# RP2040_Minimal.net
KiCad netlist of a schematic drawn in EAGLE
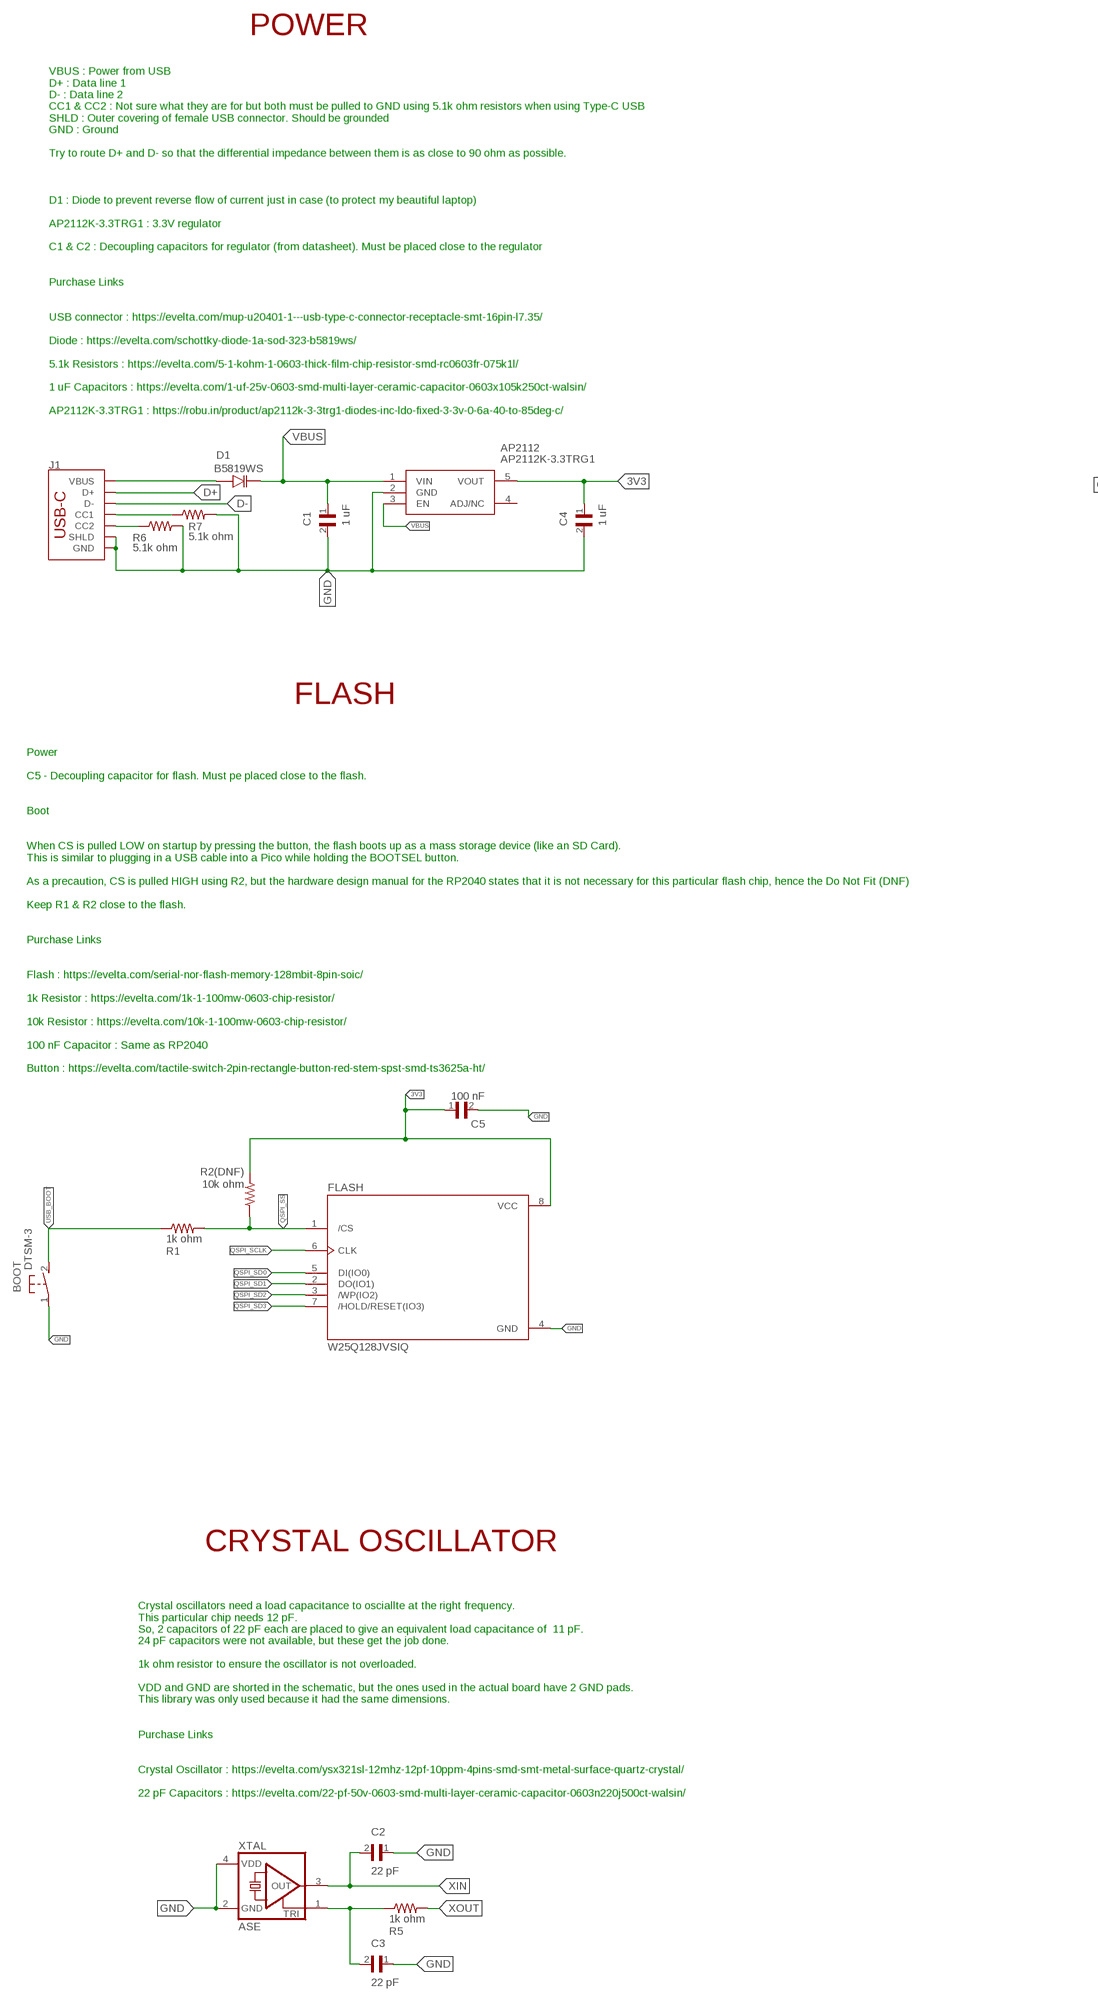
[diagram p0: schematic, sheet 1, part 1 of 2]
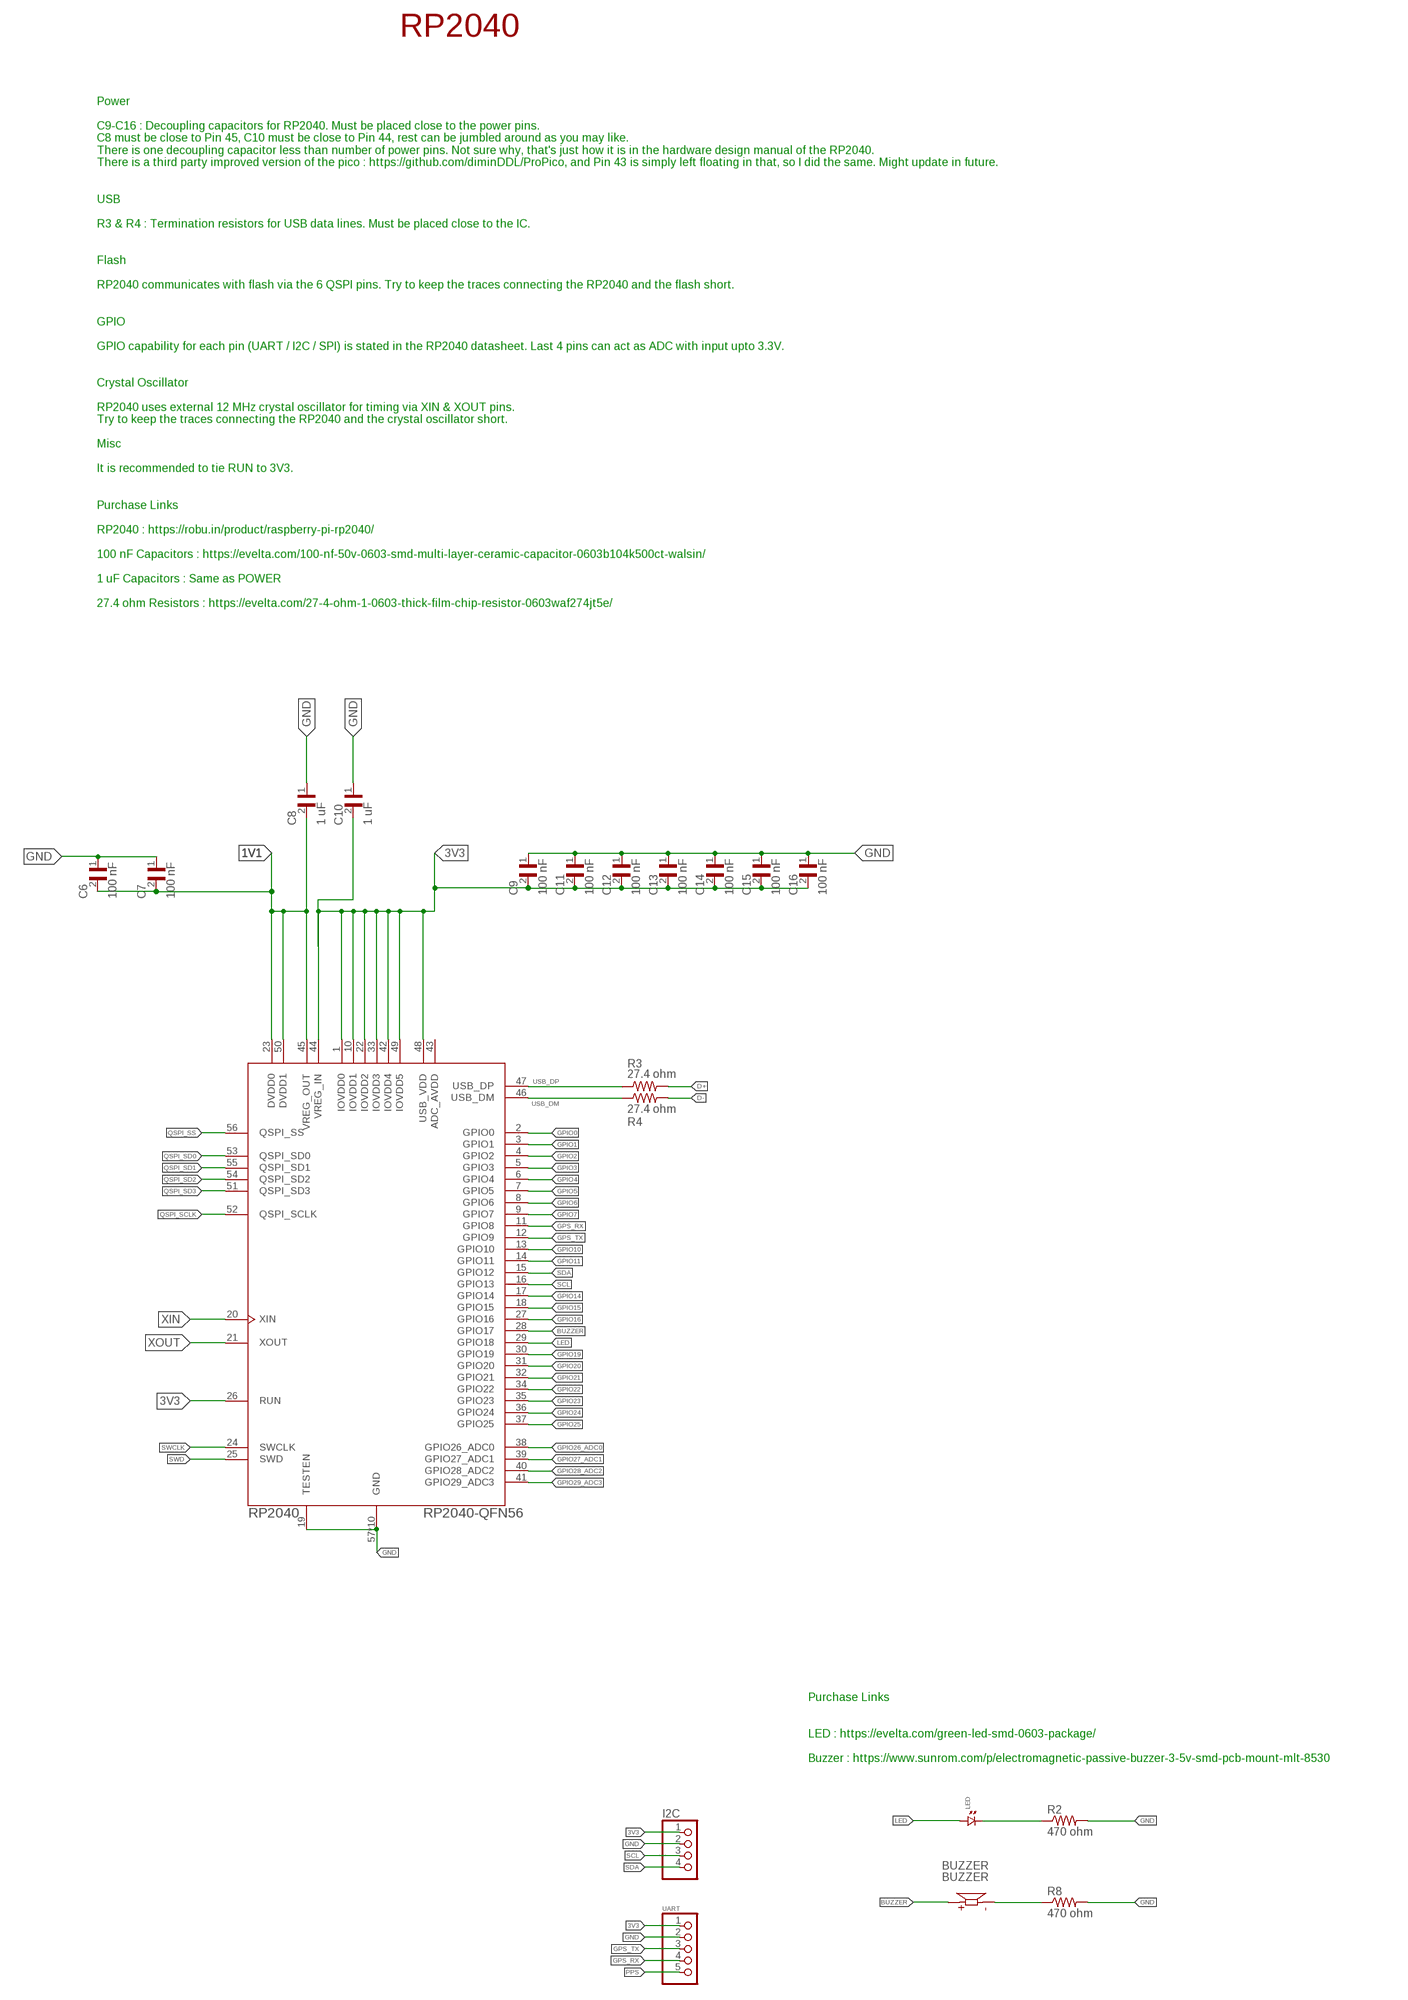
[diagram p1: schematic, sheet 1, part 2 of 2]

(export (version "E")
  (design (tool "Eeschema 10.0.6"))
  (components
    (comp (ref "AP2112")
      (value "AP2112K-3.3TRG1")
      (footprint "eagle-import:SOT95P282X130-5N")
      (fields (field (name "MOUSER_PART_NUMBER") "621-AP2112K-3.3TRG1"))
      (libsource (lib "eagle-import") (part "AP2112K-3.3TRG1"))
    )
    (comp (ref "BOOT")
      (value "DTSM-3")
      (footprint "eagle-import:DTSM-3")
      (libsource (lib "eagle-import") (part "DTSM-3"))
    )
    (comp (ref "BUZZER")
      (value "BUZZER")
      (footprint "eagle-import:CUI_CMT-8530S-SMT")
      (fields (field (name "MF") "CUI Devices") (field (name "MP") "CMT-8530S-SMT-TR"))
      (libsource (lib "eagle-import") (part "CMT-8530S-SMT"))
    )
    (comp (ref "C1")
      (value "1 uF")
      (footprint "eagle-import:CAPC1608X90")
      (fields (field (name "MF") "Yageo") (field (name "MP") "CC0603KRX7R9BB104"))
      (libsource (lib "eagle-import") (part "CC0603KRX7R9BB104"))
    )
    (comp (ref "C2")
      (value "22 pF")
      (footprint "eagle-import:CAPC1608X90")
      (fields (field (name "MF") "Yageo") (field (name "MP") "CC0603KRX7R9BB104"))
      (libsource (lib "eagle-import") (part "CC0603KRX7R9BB104"))
    )
    (comp (ref "C3")
      (value "22 pF")
      (footprint "eagle-import:CAPC1608X90")
      (fields (field (name "MF") "Yageo") (field (name "MP") "CC0603KRX7R9BB104"))
      (libsource (lib "eagle-import") (part "CC0603KRX7R9BB104"))
    )
    (comp (ref "C4")
      (value "1 uF")
      (footprint "eagle-import:CAPC1608X90")
      (fields (field (name "MF") "Yageo") (field (name "MP") "CC0603KRX7R9BB104"))
      (libsource (lib "eagle-import") (part "CC0603KRX7R9BB104"))
    )
    (comp (ref "C5")
      (value "100 nF")
      (footprint "eagle-import:CAPC1608X90")
      (fields (field (name "MF") "Yageo") (field (name "MP") "CC0603KRX7R9BB104"))
      (libsource (lib "eagle-import") (part "CC0603KRX7R9BB104"))
    )
    (comp (ref "C6")
      (value "100 nF")
      (footprint "eagle-import:CAPC1608X90")
      (fields (field (name "MF") "Yageo") (field (name "MP") "CC0603KRX7R9BB104"))
      (libsource (lib "eagle-import") (part "CC0603KRX7R9BB104"))
    )
    (comp (ref "C7")
      (value "100 nF")
      (footprint "eagle-import:CAPC1608X90")
      (fields (field (name "MF") "Yageo") (field (name "MP") "CC0603KRX7R9BB104"))
      (libsource (lib "eagle-import") (part "CC0603KRX7R9BB104"))
    )
    (comp (ref "C8")
      (value "1 uF")
      (footprint "eagle-import:CAPC1608X90")
      (fields (field (name "MF") "Yageo") (field (name "MP") "CC0603KRX7R9BB104"))
      (libsource (lib "eagle-import") (part "CC0603KRX7R9BB104"))
    )
    (comp (ref "C9")
      (value "100 nF")
      (footprint "eagle-import:CAPC1608X90")
      (fields (field (name "MF") "Yageo") (field (name "MP") "CC0603KRX7R9BB104"))
      (libsource (lib "eagle-import") (part "CC0603KRX7R9BB104"))
    )
    (comp (ref "C10")
      (value "1 uF")
      (footprint "eagle-import:CAPC1608X90")
      (fields (field (name "MF") "Yageo") (field (name "MP") "CC0603KRX7R9BB104"))
      (libsource (lib "eagle-import") (part "CC0603KRX7R9BB104"))
    )
    (comp (ref "C11")
      (value "100 nF")
      (footprint "eagle-import:CAPC1608X90")
      (fields (field (name "MF") "Yageo") (field (name "MP") "CC0603KRX7R9BB104"))
      (libsource (lib "eagle-import") (part "CC0603KRX7R9BB104"))
    )
    (comp (ref "C12")
      (value "100 nF")
      (footprint "eagle-import:CAPC1608X90")
      (fields (field (name "MF") "Yageo") (field (name "MP") "CC0603KRX7R9BB104"))
      (libsource (lib "eagle-import") (part "CC0603KRX7R9BB104"))
    )
    (comp (ref "C13")
      (value "100 nF")
      (footprint "eagle-import:CAPC1608X90")
      (fields (field (name "MF") "Yageo") (field (name "MP") "CC0603KRX7R9BB104"))
      (libsource (lib "eagle-import") (part "CC0603KRX7R9BB104"))
    )
    (comp (ref "C14")
      (value "100 nF")
      (footprint "eagle-import:CAPC1608X90")
      (fields (field (name "MF") "Yageo") (field (name "MP") "CC0603KRX7R9BB104"))
      (libsource (lib "eagle-import") (part "CC0603KRX7R9BB104"))
    )
    (comp (ref "C15")
      (value "100 nF")
      (footprint "eagle-import:CAPC1608X90")
      (fields (field (name "MF") "Yageo") (field (name "MP") "CC0603KRX7R9BB104"))
      (libsource (lib "eagle-import") (part "CC0603KRX7R9BB104"))
    )
    (comp (ref "C16")
      (value "100 nF")
      (footprint "eagle-import:CAPC1608X90")
      (fields (field (name "MF") "Yageo") (field (name "MP") "CC0603KRX7R9BB104"))
      (libsource (lib "eagle-import") (part "CC0603KRX7R9BB104"))
    )
    (comp (ref "D1")
      (value "B5819WS")
      (footprint "eagle-import:SOD2512X116N")
      (fields (field (name "MF") "Diodes Inc.") (field (name "MP") "ZMV829BTA"))
      (libsource (lib "eagle-import") (part "ZMV829BTA"))
    )
    (comp (ref "FLASH")
      (value "W25Q128JVSIQ")
      (footprint "eagle-import:SOIC127P790X216-8N")
      (fields (field (name "MF") "Winbond Electronics"))
      (libsource (lib "eagle-import") (part "W25Q128JVSIQ"))
    )
    (comp (ref "I2C")
      (value "PINHD-1X4")
      (footprint "eagle-import:1X04")
      (libsource (lib "eagle-import") (part "PINHD-1X4"))
    )
    (comp (ref "J1")
      (value "USB_C_2-LAYER_PADS")
      (footprint "eagle-import:USB-C-16P-2LAYER-PADS")
      (libsource (lib "eagle-import") (part "USB_C_2-LAYER_PADS"))
    )
    (comp (ref "LED")
      (value "LED.0603")
      (footprint "eagle-import:0603.LED")
      (libsource (lib "eagle-import") (part "LED.0603"))
    )
    (comp (ref "R1")
      (value "1k ohm")
      (footprint "eagle-import:RESC1608X50N")
      (fields
        (field (name "COMMENT") "2-1879338-7")
        (field (name "MF") "TE Connectivity")
        (field (name "MP") "CPF0603F49K9C1")
      )
      (libsource (lib "eagle-import") (part "CPF0603F49K9C1"))
    )
    (comp (ref "R2")
      (value "470 ohm")
      (footprint "eagle-import:RESC1608X50N")
      (fields
        (field (name "COMMENT") "2-1879338-7")
        (field (name "MF") "TE Connectivity")
        (field (name "MP") "CPF0603F49K9C1")
      )
      (libsource (lib "eagle-import") (part "CPF0603F49K9C1"))
    )
    (comp (ref "R2(DNF)")
      (value "10k ohm")
      (footprint "eagle-import:RESC1608X50N")
      (fields
        (field (name "COMMENT") "2-1879338-7")
        (field (name "MF") "TE Connectivity")
        (field (name "MP") "CPF0603F49K9C1")
      )
      (libsource (lib "eagle-import") (part "CPF0603F49K9C1"))
    )
    (comp (ref "R3")
      (value "27.4 ohm")
      (footprint "eagle-import:RESC1608X50N")
      (fields
        (field (name "COMMENT") "2-1879338-7")
        (field (name "MF") "TE Connectivity")
        (field (name "MP") "CPF0603F49K9C1")
      )
      (libsource (lib "eagle-import") (part "CPF0603F49K9C1"))
    )
    (comp (ref "R4")
      (value "27.4 ohm")
      (footprint "eagle-import:RESC1608X50N")
      (fields
        (field (name "COMMENT") "2-1879338-7")
        (field (name "MF") "TE Connectivity")
        (field (name "MP") "CPF0603F49K9C1")
      )
      (libsource (lib "eagle-import") (part "CPF0603F49K9C1"))
    )
    (comp (ref "R5")
      (value "1k ohm")
      (footprint "eagle-import:RESC1608X50N")
      (fields
        (field (name "COMMENT") "2-1879338-7")
        (field (name "MF") "TE Connectivity")
        (field (name "MP") "CPF0603F49K9C1")
      )
      (libsource (lib "eagle-import") (part "CPF0603F49K9C1"))
    )
    (comp (ref "R6")
      (value "5.1k ohm")
      (footprint "eagle-import:RESC1608X50N")
      (fields
        (field (name "COMMENT") "2-1879338-7")
        (field (name "MF") "TE Connectivity")
        (field (name "MP") "CPF0603F49K9C1")
      )
      (libsource (lib "eagle-import") (part "CPF0603F49K9C1"))
    )
    (comp (ref "R7")
      (value "5.1k ohm")
      (footprint "eagle-import:RESC1608X50N")
      (fields
        (field (name "COMMENT") "2-1879338-7")
        (field (name "MF") "TE Connectivity")
        (field (name "MP") "CPF0603F49K9C1")
      )
      (libsource (lib "eagle-import") (part "CPF0603F49K9C1"))
    )
    (comp (ref "R8")
      (value "470 ohm")
      (footprint "eagle-import:RESC1608X50N")
      (fields
        (field (name "COMMENT") "2-1879338-7")
        (field (name "MF") "TE Connectivity")
        (field (name "MP") "CPF0603F49K9C1")
      )
      (libsource (lib "eagle-import") (part "CPF0603F49K9C1"))
    )
    (comp (ref "RP2040")
      (value "RP2040-QFN56")
      (footprint "eagle-import:RP2040-QFN-56")
      (libsource (lib "eagle-import") (part "RP2040-QFN56"))
    )
    (comp (ref "UART")
      (value "PINHD-1X5")
      (footprint "eagle-import:1X05")
      (libsource (lib "eagle-import") (part "PINHD-1X5"))
    )
    (comp (ref "XTAL")
      (value "ASE")
      (footprint "eagle-import:ASE")
      (libsource (lib "eagle-import") (part "ASE"))
    )
  )
  (nets
    (net (code "1") (name "/ADC_AVDD") (class "Default")
      (node (ref "RP2040") (pin "43") (pinfunction "ADC_AVDD_43") (pintype "power_in"))
    )
    (net (code "2") (name "/USB_DM") (class "Default")
      (node (ref "R4") (pin "1") (pinfunction "1_1") (pintype "passive"))
      (node (ref "RP2040") (pin "46") (pinfunction "USB_DM_46") (pintype "bidirectional"))
    )
    (net (code "3") (name "/USB_DP") (class "Default")
      (node (ref "R3") (pin "1") (pinfunction "1_1") (pintype "passive"))
      (node (ref "RP2040") (pin "47") (pinfunction "USB_DP_47") (pintype "bidirectional"))
    )
    (net (code "4") (name "1V1") (class "Default")
      (node (ref "C6") (pin "2") (pinfunction "2_2") (pintype "passive"))
      (node (ref "C7") (pin "2") (pinfunction "2_2") (pintype "passive"))
      (node (ref "C8") (pin "2") (pinfunction "2_2") (pintype "passive"))
      (node (ref "RP2040") (pin "23") (pinfunction "DVDD0_23") (pintype "power_in"))
      (node (ref "RP2040") (pin "45") (pinfunction "VREG_OUT_45") (pintype "power_in"))
      (node (ref "RP2040") (pin "50") (pinfunction "DVDD1_50") (pintype "power_in"))
    )
    (net (code "5") (name "3V3") (class "Default")
      (node (ref "AP2112") (pin "5") (pinfunction "VOUT_5") (pintype "bidirectional"))
      (node (ref "C10") (pin "2") (pinfunction "2_2") (pintype "passive"))
      (node (ref "C11") (pin "2") (pinfunction "2_2") (pintype "passive"))
      (node (ref "C12") (pin "2") (pinfunction "2_2") (pintype "passive"))
      (node (ref "C13") (pin "2") (pinfunction "2_2") (pintype "passive"))
      (node (ref "C14") (pin "2") (pinfunction "2_2") (pintype "passive"))
      (node (ref "C15") (pin "2") (pinfunction "2_2") (pintype "passive"))
      (node (ref "C16") (pin "2") (pinfunction "2_2") (pintype "passive"))
      (node (ref "C4") (pin "1") (pinfunction "1_1") (pintype "passive"))
      (node (ref "C5") (pin "1") (pinfunction "1_1") (pintype "passive"))
      (node (ref "C9") (pin "2") (pinfunction "2_2") (pintype "passive"))
      (node (ref "FLASH") (pin "8") (pinfunction "VCC_8") (pintype "power_in"))
      (node (ref "I2C") (pin "1") (pinfunction "1_1") (pintype "passive"))
      (node (ref "R2(DNF)") (pin "2") (pinfunction "2_2") (pintype "passive"))
      (node (ref "RP2040") (pin "1") (pinfunction "IOVDD0_1") (pintype "power_in"))
      (node (ref "RP2040") (pin "10") (pinfunction "IOVDD1_10") (pintype "power_in"))
      (node (ref "RP2040") (pin "22") (pinfunction "IOVDD2_22") (pintype "power_in"))
      (node (ref "RP2040") (pin "26") (pinfunction "RUN_26") (pintype "input"))
      (node (ref "RP2040") (pin "33") (pinfunction "IOVDD3_33") (pintype "power_in"))
      (node (ref "RP2040") (pin "42") (pinfunction "IOVDD4_42") (pintype "power_in"))
      (node (ref "RP2040") (pin "44") (pinfunction "VREG_IN_44") (pintype "power_in"))
      (node (ref "RP2040") (pin "48") (pinfunction "USB_VDD_48") (pintype "power_in"))
      (node (ref "RP2040") (pin "49") (pinfunction "IOVDD5_49") (pintype "power_in"))
      (node (ref "UART") (pin "1") (pinfunction "1_1") (pintype "passive"))
    )
    (net (code "6") (name "BUZZER") (class "Default")
      (node (ref "BUZZER") (pin "P") (pinfunction "P_P") (pintype "passive"))
      (node (ref "RP2040") (pin "28") (pinfunction "GPIO17_28") (pintype "bidirectional"))
    )
    (net (code "7") (name "D+") (class "Default")
      (node (ref "J1") (pin "A6") (pinfunction "D+_A6") (pintype "bidirectional"))
      (node (ref "J1") (pin "B6") (pinfunction "D+_B6") (pintype "bidirectional"))
      (node (ref "R3") (pin "2") (pinfunction "2_2") (pintype "passive"))
    )
    (net (code "8") (name "D-") (class "Default")
      (node (ref "J1") (pin "A7") (pinfunction "D-_A7") (pintype "bidirectional"))
      (node (ref "J1") (pin "B7") (pinfunction "D-_B7") (pintype "bidirectional"))
      (node (ref "R4") (pin "2") (pinfunction "2_2") (pintype "passive"))
    )
    (net (code "9") (name "GND") (class "Default")
      (node (ref "AP2112") (pin "2") (pinfunction "GND_2") (pintype "bidirectional"))
      (node (ref "BOOT") (pin "1") (pinfunction "1_1") (pintype "passive"))
      (node (ref "C1") (pin "2") (pinfunction "2_2") (pintype "passive"))
      (node (ref "C10") (pin "1") (pinfunction "1_1") (pintype "passive"))
      (node (ref "C11") (pin "1") (pinfunction "1_1") (pintype "passive"))
      (node (ref "C12") (pin "1") (pinfunction "1_1") (pintype "passive"))
      (node (ref "C13") (pin "1") (pinfunction "1_1") (pintype "passive"))
      (node (ref "C14") (pin "1") (pinfunction "1_1") (pintype "passive"))
      (node (ref "C15") (pin "1") (pinfunction "1_1") (pintype "passive"))
      (node (ref "C16") (pin "1") (pinfunction "1_1") (pintype "passive"))
      (node (ref "C2") (pin "1") (pinfunction "1_1") (pintype "passive"))
      (node (ref "C3") (pin "1") (pinfunction "1_1") (pintype "passive"))
      (node (ref "C4") (pin "2") (pinfunction "2_2") (pintype "passive"))
      (node (ref "C5") (pin "2") (pinfunction "2_2") (pintype "passive"))
      (node (ref "C6") (pin "1") (pinfunction "1_1") (pintype "passive"))
      (node (ref "C7") (pin "1") (pinfunction "1_1") (pintype "passive"))
      (node (ref "C8") (pin "1") (pinfunction "1_1") (pintype "passive"))
      (node (ref "C9") (pin "1") (pinfunction "1_1") (pintype "passive"))
      (node (ref "FLASH") (pin "4") (pinfunction "GND_4") (pintype "power_in"))
      (node (ref "I2C") (pin "2") (pinfunction "2_2") (pintype "passive"))
      (node (ref "J1") (pin "GND") (pinfunction "GND_GND") (pintype "bidirectional"))
      (node (ref "J1") (pin "GND2") (pinfunction "GND_GND2") (pintype "bidirectional"))
      (node (ref "J1") (pin "SHLD1") (pinfunction "SHLD_SHLD1") (pintype "bidirectional"))
      (node (ref "J1") (pin "SHLD2") (pinfunction "SHLD_SHLD2") (pintype "bidirectional"))
      (node (ref "J1") (pin "SHLD3") (pinfunction "SHLD_SHLD3") (pintype "bidirectional"))
      (node (ref "J1") (pin "SHLD4") (pinfunction "SHLD_SHLD4") (pintype "bidirectional"))
      (node (ref "R2") (pin "2") (pinfunction "2_2") (pintype "passive"))
      (node (ref "R6") (pin "2") (pinfunction "2_2") (pintype "passive"))
      (node (ref "R7") (pin "2") (pinfunction "2_2") (pintype "passive"))
      (node (ref "R8") (pin "2") (pinfunction "2_2") (pintype "passive"))
      (node (ref "RP2040") (pin "19") (pinfunction "TESTEN_19") (pintype "passive"))
      (node (ref "RP2040") (pin "57") (pinfunction "GND_57") (pintype "power_in"))
      (node (ref "RP2040") (pin "58") (pinfunction "GND_58") (pintype "power_in"))
      (node (ref "RP2040") (pin "59") (pinfunction "GND_59") (pintype "power_in"))
      (node (ref "RP2040") (pin "60") (pinfunction "GND_60") (pintype "power_in"))
      (node (ref "RP2040") (pin "61") (pinfunction "GND_61") (pintype "power_in"))
      (node (ref "RP2040") (pin "62") (pinfunction "GND_62") (pintype "power_in"))
      (node (ref "RP2040") (pin "63") (pinfunction "GND_63") (pintype "power_in"))
      (node (ref "RP2040") (pin "64") (pinfunction "GND_64") (pintype "power_in"))
      (node (ref "RP2040") (pin "65") (pinfunction "GND_65") (pintype "power_in"))
      (node (ref "RP2040") (pin "66") (pinfunction "GND_66") (pintype "power_in"))
      (node (ref "UART") (pin "2") (pinfunction "2_2") (pintype "passive"))
      (node (ref "XTAL") (pin "2") (pinfunction "GND_2") (pintype "power_in"))
      (node (ref "XTAL") (pin "4") (pinfunction "VDD_4") (pintype "power_in"))
    )
    (net (code "10") (name "GPIO0") (class "Default")
      (node (ref "RP2040") (pin "2") (pinfunction "GPIO0_2") (pintype "bidirectional"))
    )
    (net (code "11") (name "GPIO1") (class "Default")
      (node (ref "RP2040") (pin "3") (pinfunction "GPIO1_3") (pintype "bidirectional"))
    )
    (net (code "12") (name "GPIO2") (class "Default")
      (node (ref "RP2040") (pin "4") (pinfunction "GPIO2_4") (pintype "bidirectional"))
    )
    (net (code "13") (name "GPIO3") (class "Default")
      (node (ref "RP2040") (pin "5") (pinfunction "GPIO3_5") (pintype "bidirectional"))
    )
    (net (code "14") (name "GPIO4") (class "Default")
      (node (ref "RP2040") (pin "6") (pinfunction "GPIO4_6") (pintype "bidirectional"))
    )
    (net (code "15") (name "GPIO5") (class "Default")
      (node (ref "RP2040") (pin "7") (pinfunction "GPIO5_7") (pintype "bidirectional"))
    )
    (net (code "16") (name "GPIO6") (class "Default")
      (node (ref "RP2040") (pin "8") (pinfunction "GPIO6_8") (pintype "bidirectional"))
    )
    (net (code "17") (name "GPIO7") (class "Default")
      (node (ref "RP2040") (pin "9") (pinfunction "GPIO7_9") (pintype "bidirectional"))
    )
    (net (code "18") (name "GPIO10") (class "Default")
      (node (ref "RP2040") (pin "13") (pinfunction "GPIO10_13") (pintype "bidirectional"))
    )
    (net (code "19") (name "GPIO11") (class "Default")
      (node (ref "RP2040") (pin "14") (pinfunction "GPIO11_14") (pintype "bidirectional"))
    )
    (net (code "20") (name "GPIO14") (class "Default")
      (node (ref "RP2040") (pin "17") (pinfunction "GPIO14_17") (pintype "bidirectional"))
    )
    (net (code "21") (name "GPIO15") (class "Default")
      (node (ref "RP2040") (pin "18") (pinfunction "GPIO15_18") (pintype "bidirectional"))
    )
    (net (code "22") (name "GPIO16") (class "Default")
      (node (ref "RP2040") (pin "27") (pinfunction "GPIO16_27") (pintype "bidirectional"))
    )
    (net (code "23") (name "GPIO19") (class "Default")
      (node (ref "RP2040") (pin "30") (pinfunction "GPIO19_30") (pintype "bidirectional"))
    )
    (net (code "24") (name "GPIO20") (class "Default")
      (node (ref "RP2040") (pin "31") (pinfunction "GPIO20_31") (pintype "bidirectional"))
    )
    (net (code "25") (name "GPIO21") (class "Default")
      (node (ref "RP2040") (pin "32") (pinfunction "GPIO21_32") (pintype "bidirectional"))
    )
    (net (code "26") (name "GPIO22") (class "Default")
      (node (ref "RP2040") (pin "34") (pinfunction "GPIO22_34") (pintype "bidirectional"))
    )
    (net (code "27") (name "GPIO23") (class "Default")
      (node (ref "RP2040") (pin "35") (pinfunction "GPIO23_35") (pintype "bidirectional"))
    )
    (net (code "28") (name "GPIO24") (class "Default")
      (node (ref "RP2040") (pin "36") (pinfunction "GPIO24_36") (pintype "bidirectional"))
    )
    (net (code "29") (name "GPIO25") (class "Default")
      (node (ref "RP2040") (pin "37") (pinfunction "GPIO25_37") (pintype "bidirectional"))
    )
    (net (code "30") (name "GPIO26_ADC0") (class "Default")
      (node (ref "RP2040") (pin "38") (pinfunction "GPIO26_ADC0_38") (pintype "bidirectional"))
    )
    (net (code "31") (name "GPIO27_ADC1") (class "Default")
      (node (ref "RP2040") (pin "39") (pinfunction "GPIO27_ADC1_39") (pintype "bidirectional"))
    )
    (net (code "32") (name "GPIO28_ADC2") (class "Default")
      (node (ref "RP2040") (pin "40") (pinfunction "GPIO28_ADC2_40") (pintype "bidirectional"))
    )
    (net (code "33") (name "GPIO29_ADC3") (class "Default")
      (node (ref "RP2040") (pin "41") (pinfunction "GPIO29_ADC3_41") (pintype "bidirectional"))
    )
    (net (code "34") (name "GPS_RX") (class "Default")
      (node (ref "RP2040") (pin "11") (pinfunction "GPIO8_11") (pintype "bidirectional"))
      (node (ref "UART") (pin "4") (pinfunction "4_4") (pintype "passive"))
    )
    (net (code "35") (name "GPS_TX") (class "Default")
      (node (ref "RP2040") (pin "12") (pinfunction "GPIO9_12") (pintype "bidirectional"))
      (node (ref "UART") (pin "3") (pinfunction "3_3") (pintype "passive"))
    )
    (net (code "36") (name "LED") (class "Default")
      (node (ref "LED") (pin "P$1") (pinfunction "1_P$1") (pintype "bidirectional"))
      (node (ref "RP2040") (pin "29") (pinfunction "GPIO18_29") (pintype "bidirectional"))
    )
    (net (code "37") (name "Net-(BUZZER-PadN)") (class "Default")
      (node (ref "BUZZER") (pin "N") (pinfunction "N_N") (pintype "passive"))
      (node (ref "R8") (pin "1") (pinfunction "1_1") (pintype "passive"))
    )
    (net (code "38") (name "Net-(D1-PadA)") (class "Default")
      (node (ref "D1") (pin "A") (pinfunction "A_A") (pintype "passive"))
      (node (ref "J1") (pin "VBUS1") (pinfunction "VBUS_VBUS1") (pintype "bidirectional"))
      (node (ref "J1") (pin "VBUS2") (pinfunction "VBUS_VBUS2") (pintype "bidirectional"))
    )
    (net (code "39") (name "Net-(J1-CC1)") (class "Default")
      (node (ref "J1") (pin "A5") (pinfunction "CC1_A5") (pintype "bidirectional"))
      (node (ref "R7") (pin "1") (pinfunction "1_1") (pintype "passive"))
    )
    (net (code "40") (name "Net-(J1-CC2)") (class "Default")
      (node (ref "J1") (pin "B5") (pinfunction "CC2_B5") (pintype "bidirectional"))
      (node (ref "R6") (pin "1") (pinfunction "1_1") (pintype "passive"))
    )
    (net (code "41") (name "Net-(LED-2)") (class "Default")
      (node (ref "LED") (pin "P$2") (pinfunction "2_P$2") (pintype "bidirectional"))
      (node (ref "R2") (pin "1") (pinfunction "1_1") (pintype "passive"))
    )
    (net (code "42") (name "Net-(XTAL-TRI)") (class "Default")
      (node (ref "C3") (pin "2") (pinfunction "2_2") (pintype "passive"))
      (node (ref "R5") (pin "1") (pinfunction "1_1") (pintype "passive"))
      (node (ref "XTAL") (pin "1") (pinfunction "TRI_1") (pintype "input"))
    )
    (net (code "43") (name "PPS") (class "Default")
      (node (ref "UART") (pin "5") (pinfunction "5_5") (pintype "passive"))
    )
    (net (code "44") (name "QSPI_SCLK") (class "Default")
      (node (ref "FLASH") (pin "6") (pinfunction "CLK_6") (pintype "input"))
      (node (ref "RP2040") (pin "52") (pinfunction "QSPI_SCLK_52") (pintype "output"))
    )
    (net (code "45") (name "QSPI_SD0") (class "Default")
      (node (ref "FLASH") (pin "5") (pinfunction "DI(IO0)_5") (pintype "bidirectional"))
      (node (ref "RP2040") (pin "53") (pinfunction "QSPI_SD0_53") (pintype "bidirectional"))
    )
    (net (code "46") (name "QSPI_SD1") (class "Default")
      (node (ref "FLASH") (pin "2") (pinfunction "DO(IO1)_2") (pintype "bidirectional"))
      (node (ref "RP2040") (pin "55") (pinfunction "QSPI_SD1_55") (pintype "bidirectional"))
    )
    (net (code "47") (name "QSPI_SD2") (class "Default")
      (node (ref "FLASH") (pin "3") (pinfunction "/WP(IO2)_3") (pintype "bidirectional"))
      (node (ref "RP2040") (pin "54") (pinfunction "QSPI_SD2_54") (pintype "bidirectional"))
    )
    (net (code "48") (name "QSPI_SD3") (class "Default")
      (node (ref "FLASH") (pin "7") (pinfunction "/HOLD/RESET(IO3)_7") (pintype "bidirectional"))
      (node (ref "RP2040") (pin "51") (pinfunction "QSPI_SD3_51") (pintype "bidirectional"))
    )
    (net (code "49") (name "QSPI_SS") (class "Default")
      (node (ref "FLASH") (pin "1") (pinfunction "/CS_1") (pintype "input"))
      (node (ref "R1") (pin "2") (pinfunction "2_2") (pintype "passive"))
      (node (ref "R2(DNF)") (pin "1") (pinfunction "1_1") (pintype "passive"))
      (node (ref "RP2040") (pin "56") (pinfunction "QSPI_SS_56") (pintype "bidirectional"))
    )
    (net (code "50") (name "SCL") (class "Default")
      (node (ref "I2C") (pin "3") (pinfunction "3_3") (pintype "passive"))
      (node (ref "RP2040") (pin "16") (pinfunction "GPIO13_16") (pintype "bidirectional"))
    )
    (net (code "51") (name "SDA") (class "Default")
      (node (ref "I2C") (pin "4") (pinfunction "4_4") (pintype "passive"))
      (node (ref "RP2040") (pin "15") (pinfunction "GPIO12_15") (pintype "bidirectional"))
    )
    (net (code "52") (name "SWCLK") (class "Default")
      (node (ref "RP2040") (pin "24") (pinfunction "SWCLK_24") (pintype "output"))
    )
    (net (code "53") (name "SWD") (class "Default")
      (node (ref "RP2040") (pin "25") (pinfunction "SWD_25") (pintype "bidirectional"))
    )
    (net (code "54") (name "USB_BOOT") (class "Default")
      (node (ref "BOOT") (pin "2") (pinfunction "2_2") (pintype "passive"))
      (node (ref "R1") (pin "1") (pinfunction "1_1") (pintype "passive"))
    )
    (net (code "55") (name "VBUS") (class "Default")
      (node (ref "AP2112") (pin "1") (pinfunction "VIN_1") (pintype "bidirectional"))
      (node (ref "AP2112") (pin "3") (pinfunction "EN_3") (pintype "bidirectional"))
      (node (ref "C1") (pin "1") (pinfunction "1_1") (pintype "passive"))
      (node (ref "D1") (pin "K") (pinfunction "K_K") (pintype "passive"))
    )
    (net (code "56") (name "XIN") (class "Default")
      (node (ref "C2") (pin "2") (pinfunction "2_2") (pintype "passive"))
      (node (ref "RP2040") (pin "20") (pinfunction "XIN_20") (pintype "input"))
      (node (ref "XTAL") (pin "3") (pinfunction "OUT_3") (pintype "output"))
    )
    (net (code "57") (name "XOUT") (class "Default")
      (node (ref "R5") (pin "2") (pinfunction "2_2") (pintype "passive"))
      (node (ref "RP2040") (pin "21") (pinfunction "XOUT_21") (pintype "passive"))
    )
    (net (code "58") (name "unconnected-(AP2112-ADJ{slash}NC-Pad4)") (class "Default")
      (node (ref "AP2112") (pin "4") (pinfunction "ADJ/NC_4") (pintype "bidirectional"))
    )
  )
)
